# mail-mailer.net
KiCad netlist of a schematic drawn in EAGLE
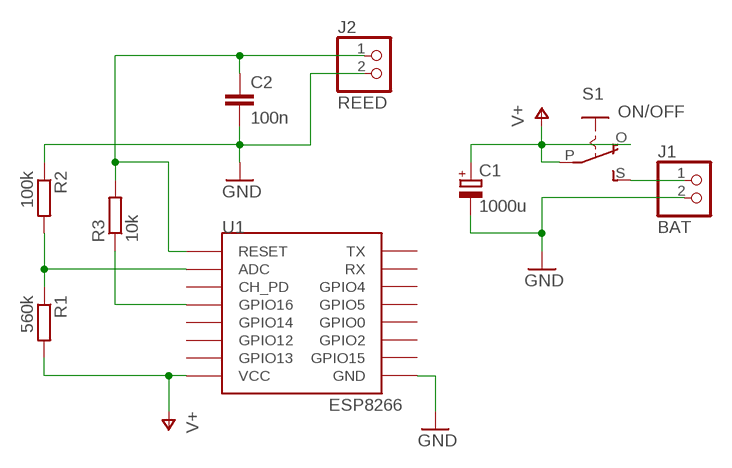
[diagram p0: schematic, sheet 1]

(export (version "E")
  (design (tool "Eeschema 10.0.6"))
  (components
    (comp (ref "C1")
      (value "1000u")
      (footprint "eagle-import:E3,5-10")
      (libsource (lib "eagle-import") (part "CPOL-EUE3.5-10"))
    )
    (comp (ref "C2")
      (value "100n")
      (footprint "eagle-import:C025-025X050")
      (libsource (lib "eagle-import") (part "C-EU025-025X050"))
    )
    (comp (ref "J1")
      (value "BAT")
      (footprint "eagle-import:1X02")
      (libsource (lib "eagle-import") (part "PINHD-1X2"))
    )
    (comp (ref "J2")
      (value "REED")
      (footprint "eagle-import:1X02")
      (libsource (lib "eagle-import") (part "PINHD-1X2"))
    )
    (comp (ref "R1")
      (value "560k")
      (footprint "eagle-import:0204_7")
      (libsource (lib "eagle-import") (part "R-EU_0204/7"))
    )
    (comp (ref "R2")
      (value "100k")
      (footprint "eagle-import:0204_7")
      (libsource (lib "eagle-import") (part "R-EU_0204/7"))
    )
    (comp (ref "R3")
      (value "10k")
      (footprint "eagle-import:0204_7")
      (libsource (lib "eagle-import") (part "R-EU_0204/7"))
    )
    (comp (ref "S1")
      (value "ON/OFF")
      (footprint "eagle-import:EG1218")
      (libsource (lib "eagle-import") (part "EG1218S"))
    )
    (comp (ref "U1")
      (value "ESP8266")
      (footprint "eagle-import:ESP-12-BREAKOUT")
      (libsource (lib "eagle-import") (part "ESP12EDIP"))
    )
  )
  (nets
    (net (code "1") (name "GND") (class "Default")
      (node (ref "C1") (pin "-") (pinfunction "-_-") (pintype "passive"))
      (node (ref "C2") (pin "2") (pinfunction "2_2") (pintype "passive"))
      (node (ref "J1") (pin "2") (pinfunction "2_2") (pintype "passive"))
      (node (ref "J2") (pin "2") (pinfunction "2_2") (pintype "passive"))
      (node (ref "R2") (pin "1") (pinfunction "1_1") (pintype "passive"))
      (node (ref "U1") (pin "P$9") (pinfunction "GND_P$9") (pintype "bidirectional"))
    )
    (net (code "2") (name "Net-(J1-Pad1)") (class "Default")
      (node (ref "J1") (pin "1") (pinfunction "1_1") (pintype "passive"))
      (node (ref "S1") (pin "S") (pinfunction "S_S") (pintype "passive"))
    )
    (net (code "3") (name "Net-(U1-ADC)") (class "Default")
      (node (ref "R1") (pin "1") (pinfunction "1_1") (pintype "passive"))
      (node (ref "R2") (pin "2") (pinfunction "2_2") (pintype "passive"))
      (node (ref "U1") (pin "P$7") (pinfunction "ADC_P$7") (pintype "bidirectional"))
    )
    (net (code "4") (name "Net-(U1-GPIO16)") (class "Default")
      (node (ref "R3") (pin "1") (pinfunction "1_1") (pintype "passive"))
      (node (ref "U1") (pin "P$5") (pinfunction "GPIO16_P$5") (pintype "bidirectional"))
    )
    (net (code "5") (name "Net-(U1-RESET)") (class "Default")
      (node (ref "C2") (pin "1") (pinfunction "1_1") (pintype "passive"))
      (node (ref "J2") (pin "1") (pinfunction "1_1") (pintype "passive"))
      (node (ref "R3") (pin "2") (pinfunction "2_2") (pintype "passive"))
      (node (ref "U1") (pin "P$8") (pinfunction "RESET_P$8") (pintype "bidirectional"))
    )
    (net (code "6") (name "V+") (class "Default")
      (node (ref "C1") (pin "+") (pinfunction "+_+") (pintype "passive"))
      (node (ref "R1") (pin "2") (pinfunction "2_2") (pintype "passive"))
      (node (ref "S1") (pin "O") (pinfunction "O_O") (pintype "passive"))
      (node (ref "S1") (pin "P") (pinfunction "P_P") (pintype "passive"))
      (node (ref "U1") (pin "P$1") (pinfunction "VCC_P$1") (pintype "bidirectional"))
    )
    (net (code "7") (name "unconnected-(U1-CH_PD-PadP$6)") (class "Default")
      (node (ref "U1") (pin "P$6") (pinfunction "CH_PD_P$6") (pintype "bidirectional"))
    )
    (net (code "8") (name "unconnected-(U1-GPIO0-PadP$12)") (class "Default")
      (node (ref "U1") (pin "P$12") (pinfunction "GPIO0_P$12") (pintype "bidirectional"))
    )
    (net (code "9") (name "unconnected-(U1-GPIO2-PadP$11)") (class "Default")
      (node (ref "U1") (pin "P$11") (pinfunction "GPIO2_P$11") (pintype "bidirectional"))
    )
    (net (code "10") (name "unconnected-(U1-GPIO4-PadP$14)") (class "Default")
      (node (ref "U1") (pin "P$14") (pinfunction "GPIO4_P$14") (pintype "bidirectional"))
    )
    (net (code "11") (name "unconnected-(U1-GPIO5-PadP$13)") (class "Default")
      (node (ref "U1") (pin "P$13") (pinfunction "GPIO5_P$13") (pintype "bidirectional"))
    )
    (net (code "12") (name "unconnected-(U1-GPIO12-PadP$3)") (class "Default")
      (node (ref "U1") (pin "P$3") (pinfunction "GPIO12_P$3") (pintype "bidirectional"))
    )
    (net (code "13") (name "unconnected-(U1-GPIO13-PadP$2)") (class "Default")
      (node (ref "U1") (pin "P$2") (pinfunction "GPIO13_P$2") (pintype "bidirectional"))
    )
    (net (code "14") (name "unconnected-(U1-GPIO14-PadP$4)") (class "Default")
      (node (ref "U1") (pin "P$4") (pinfunction "GPIO14_P$4") (pintype "bidirectional"))
    )
    (net (code "15") (name "unconnected-(U1-GPIO15-PadP$10)") (class "Default")
      (node (ref "U1") (pin "P$10") (pinfunction "GPIO15_P$10") (pintype "bidirectional"))
    )
    (net (code "16") (name "unconnected-(U1-RX-PadP$15)") (class "Default")
      (node (ref "U1") (pin "P$15") (pinfunction "RX_P$15") (pintype "bidirectional"))
    )
    (net (code "17") (name "unconnected-(U1-TX-PadP$16)") (class "Default")
      (node (ref "U1") (pin "P$16") (pinfunction "TX_P$16") (pintype "bidirectional"))
    )
  )
)
